# test_controller.net
KiCad netlist of a schematic drawn in EAGLE
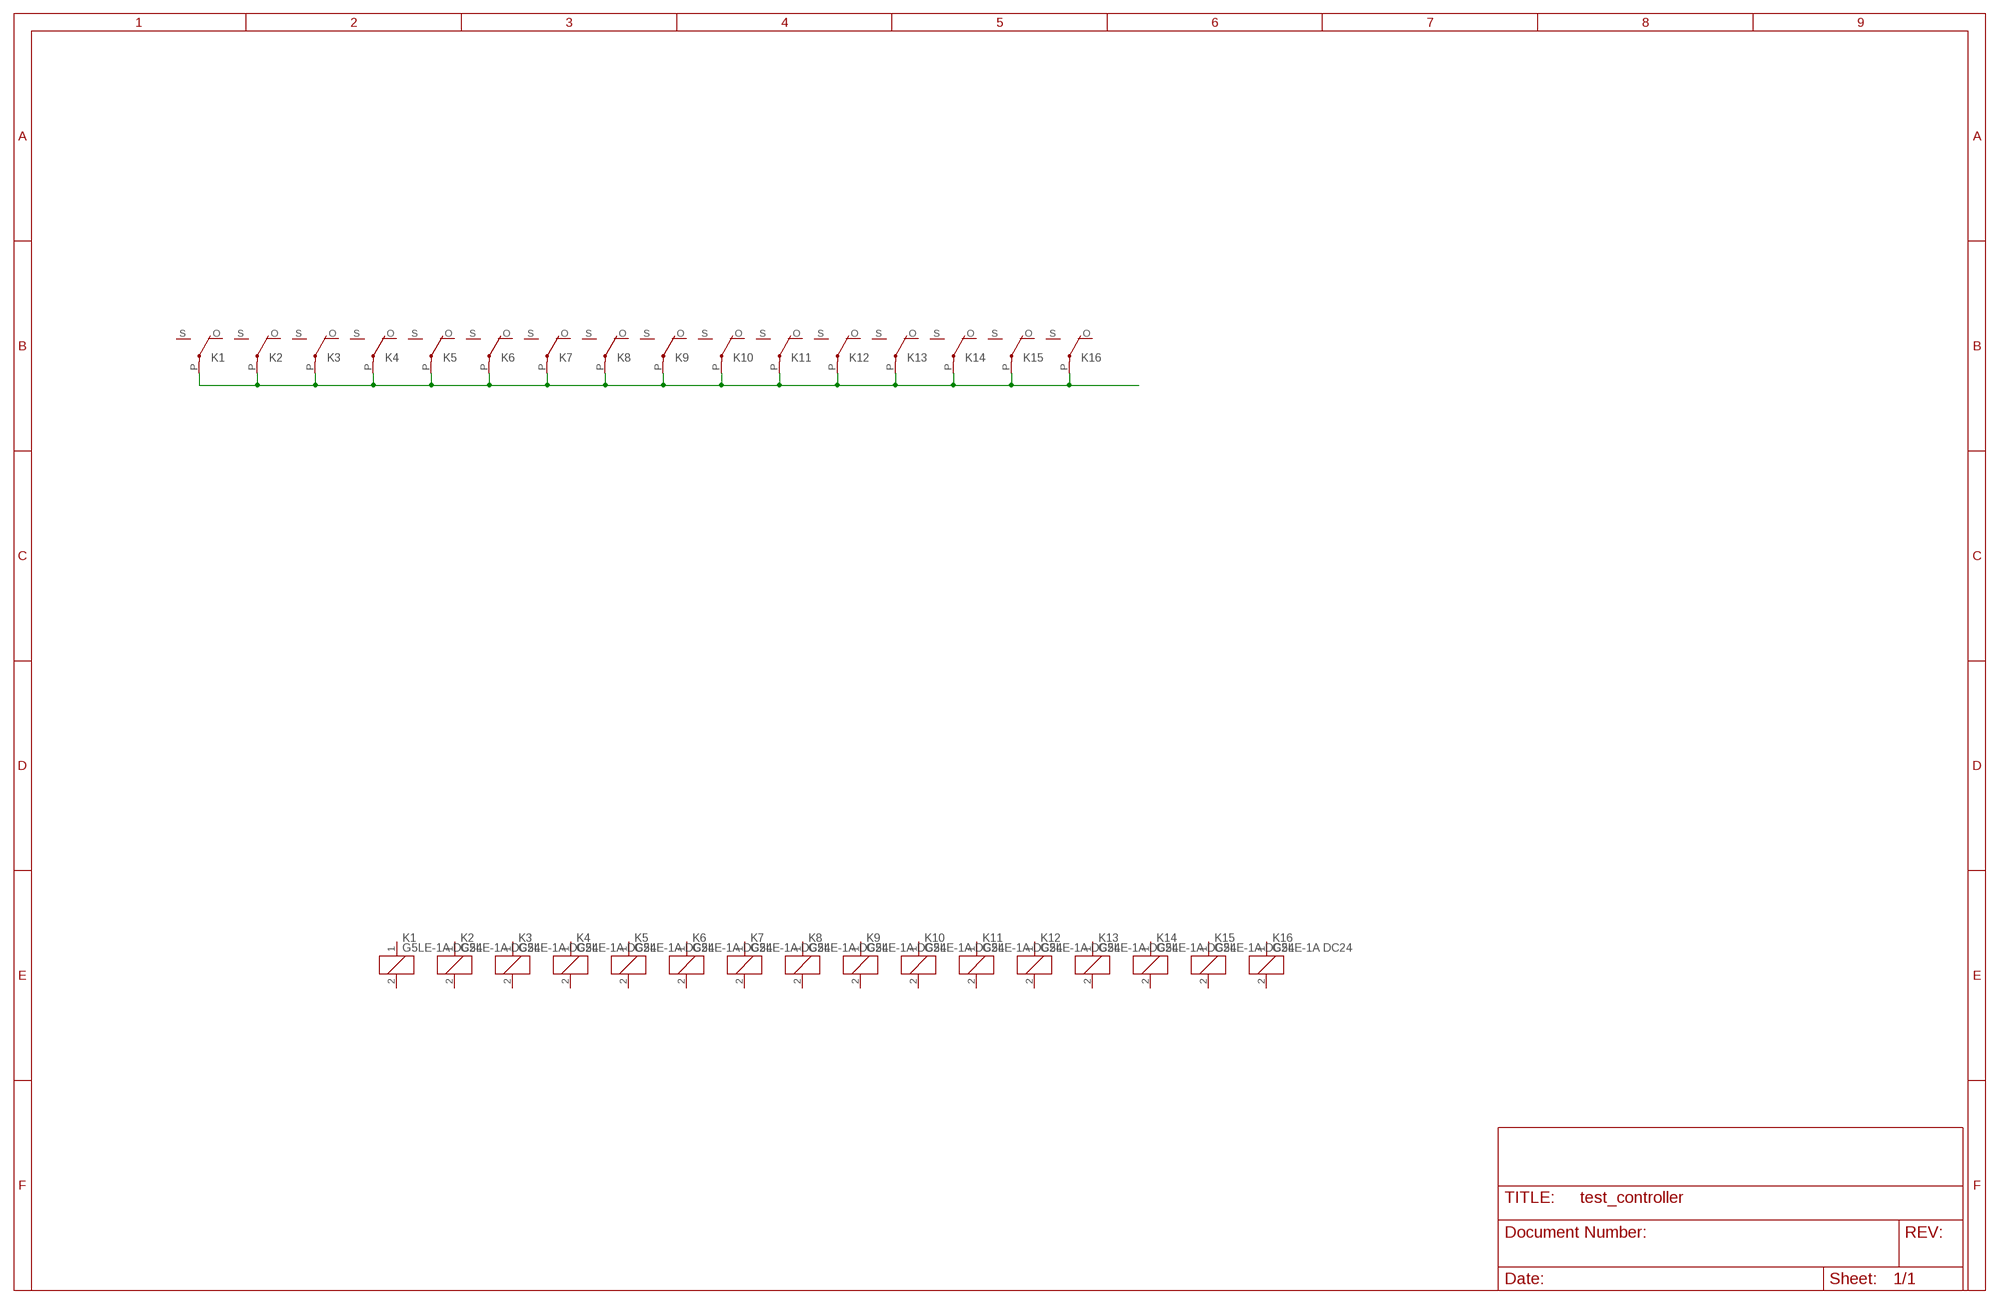
[diagram p0: schematic, sheet 1]

(export (version "E")
  (design (tool "Eeschema 10.0.6"))
  (components
    (comp (ref "K1")
      (value "G5LE-1A DC24")
      (footprint "eagle-import:G5LE")
      (libsource (lib "eagle-import") (part "G5LE"))
    )
    (comp (ref "K2")
      (value "G5LE-1A DC24")
      (footprint "eagle-import:G5LE")
      (libsource (lib "eagle-import") (part "G5LE"))
    )
    (comp (ref "K3")
      (value "G5LE-1A DC24")
      (footprint "eagle-import:G5LE")
      (libsource (lib "eagle-import") (part "G5LE"))
    )
    (comp (ref "K4")
      (value "G5LE-1A DC24")
      (footprint "eagle-import:G5LE")
      (libsource (lib "eagle-import") (part "G5LE"))
    )
    (comp (ref "K5")
      (value "G5LE-1A DC24")
      (footprint "eagle-import:G5LE")
      (libsource (lib "eagle-import") (part "G5LE"))
    )
    (comp (ref "K6")
      (value "G5LE-1A DC24")
      (footprint "eagle-import:G5LE")
      (libsource (lib "eagle-import") (part "G5LE"))
    )
    (comp (ref "K7")
      (value "G5LE-1A DC24")
      (footprint "eagle-import:G5LE")
      (libsource (lib "eagle-import") (part "G5LE"))
    )
    (comp (ref "K8")
      (value "G5LE-1A DC24")
      (footprint "eagle-import:G5LE")
      (libsource (lib "eagle-import") (part "G5LE"))
    )
    (comp (ref "K9")
      (value "G5LE-1A DC24")
      (footprint "eagle-import:G5LE")
      (libsource (lib "eagle-import") (part "G5LE"))
    )
    (comp (ref "K10")
      (value "G5LE-1A DC24")
      (footprint "eagle-import:G5LE")
      (libsource (lib "eagle-import") (part "G5LE"))
    )
    (comp (ref "K11")
      (value "G5LE-1A DC24")
      (footprint "eagle-import:G5LE")
      (libsource (lib "eagle-import") (part "G5LE"))
    )
    (comp (ref "K12")
      (value "G5LE-1A DC24")
      (footprint "eagle-import:G5LE")
      (libsource (lib "eagle-import") (part "G5LE"))
    )
    (comp (ref "K13")
      (value "G5LE-1A DC24")
      (footprint "eagle-import:G5LE")
      (libsource (lib "eagle-import") (part "G5LE"))
    )
    (comp (ref "K14")
      (value "G5LE-1A DC24")
      (footprint "eagle-import:G5LE")
      (libsource (lib "eagle-import") (part "G5LE"))
    )
    (comp (ref "K15")
      (value "G5LE-1A DC24")
      (footprint "eagle-import:G5LE")
      (libsource (lib "eagle-import") (part "G5LE"))
    )
    (comp (ref "K16")
      (value "G5LE-1A DC24")
      (footprint "eagle-import:G5LE")
      (libsource (lib "eagle-import") (part "G5LE"))
    )
  )
  (nets
    (net (code "1") (name "Net-(K1-PadP)") (class "Default")
      (node (ref "K1") (pin "P") (pinfunction "P_P") (pintype "passive"))
      (node (ref "K10") (pin "P") (pinfunction "P_P") (pintype "passive"))
      (node (ref "K11") (pin "P") (pinfunction "P_P") (pintype "passive"))
      (node (ref "K12") (pin "P") (pinfunction "P_P") (pintype "passive"))
      (node (ref "K13") (pin "P") (pinfunction "P_P") (pintype "passive"))
      (node (ref "K14") (pin "P") (pinfunction "P_P") (pintype "passive"))
      (node (ref "K15") (pin "P") (pinfunction "P_P") (pintype "passive"))
      (node (ref "K16") (pin "P") (pinfunction "P_P") (pintype "passive"))
      (node (ref "K2") (pin "P") (pinfunction "P_P") (pintype "passive"))
      (node (ref "K3") (pin "P") (pinfunction "P_P") (pintype "passive"))
      (node (ref "K4") (pin "P") (pinfunction "P_P") (pintype "passive"))
      (node (ref "K5") (pin "P") (pinfunction "P_P") (pintype "passive"))
      (node (ref "K6") (pin "P") (pinfunction "P_P") (pintype "passive"))
      (node (ref "K7") (pin "P") (pinfunction "P_P") (pintype "passive"))
      (node (ref "K8") (pin "P") (pinfunction "P_P") (pintype "passive"))
      (node (ref "K9") (pin "P") (pinfunction "P_P") (pintype "passive"))
    )
    (net (code "2") (name "unconnected-(K1-Pad1)") (class "Default")
      (node (ref "K1") (pin "1") (pinfunction "1_1") (pintype "passive"))
    )
    (net (code "3") (name "unconnected-(K1-Pad2)") (class "Default")
      (node (ref "K1") (pin "2") (pinfunction "2_2") (pintype "passive"))
    )
    (net (code "4") (name "unconnected-(K1-PadO)") (class "Default")
      (node (ref "K1") (pin "O") (pinfunction "O_O") (pintype "passive"))
    )
    (net (code "5") (name "unconnected-(K1-PadS)") (class "Default")
      (node (ref "K1") (pin "S") (pinfunction "S_S") (pintype "passive"))
    )
    (net (code "6") (name "unconnected-(K2-Pad1)") (class "Default")
      (node (ref "K2") (pin "1") (pinfunction "1_1") (pintype "passive"))
    )
    (net (code "7") (name "unconnected-(K2-Pad2)") (class "Default")
      (node (ref "K2") (pin "2") (pinfunction "2_2") (pintype "passive"))
    )
    (net (code "8") (name "unconnected-(K2-PadO)") (class "Default")
      (node (ref "K2") (pin "O") (pinfunction "O_O") (pintype "passive"))
    )
    (net (code "9") (name "unconnected-(K2-PadS)") (class "Default")
      (node (ref "K2") (pin "S") (pinfunction "S_S") (pintype "passive"))
    )
    (net (code "10") (name "unconnected-(K3-Pad1)") (class "Default")
      (node (ref "K3") (pin "1") (pinfunction "1_1") (pintype "passive"))
    )
    (net (code "11") (name "unconnected-(K3-Pad2)") (class "Default")
      (node (ref "K3") (pin "2") (pinfunction "2_2") (pintype "passive"))
    )
    (net (code "12") (name "unconnected-(K3-PadO)") (class "Default")
      (node (ref "K3") (pin "O") (pinfunction "O_O") (pintype "passive"))
    )
    (net (code "13") (name "unconnected-(K3-PadS)") (class "Default")
      (node (ref "K3") (pin "S") (pinfunction "S_S") (pintype "passive"))
    )
    (net (code "14") (name "unconnected-(K4-Pad1)") (class "Default")
      (node (ref "K4") (pin "1") (pinfunction "1_1") (pintype "passive"))
    )
    (net (code "15") (name "unconnected-(K4-Pad2)") (class "Default")
      (node (ref "K4") (pin "2") (pinfunction "2_2") (pintype "passive"))
    )
    (net (code "16") (name "unconnected-(K4-PadO)") (class "Default")
      (node (ref "K4") (pin "O") (pinfunction "O_O") (pintype "passive"))
    )
    (net (code "17") (name "unconnected-(K4-PadS)") (class "Default")
      (node (ref "K4") (pin "S") (pinfunction "S_S") (pintype "passive"))
    )
    (net (code "18") (name "unconnected-(K5-Pad1)") (class "Default")
      (node (ref "K5") (pin "1") (pinfunction "1_1") (pintype "passive"))
    )
    (net (code "19") (name "unconnected-(K5-Pad2)") (class "Default")
      (node (ref "K5") (pin "2") (pinfunction "2_2") (pintype "passive"))
    )
    (net (code "20") (name "unconnected-(K5-PadO)") (class "Default")
      (node (ref "K5") (pin "O") (pinfunction "O_O") (pintype "passive"))
    )
    (net (code "21") (name "unconnected-(K5-PadS)") (class "Default")
      (node (ref "K5") (pin "S") (pinfunction "S_S") (pintype "passive"))
    )
    (net (code "22") (name "unconnected-(K6-Pad1)") (class "Default")
      (node (ref "K6") (pin "1") (pinfunction "1_1") (pintype "passive"))
    )
    (net (code "23") (name "unconnected-(K6-Pad2)") (class "Default")
      (node (ref "K6") (pin "2") (pinfunction "2_2") (pintype "passive"))
    )
    (net (code "24") (name "unconnected-(K6-PadO)") (class "Default")
      (node (ref "K6") (pin "O") (pinfunction "O_O") (pintype "passive"))
    )
    (net (code "25") (name "unconnected-(K6-PadS)") (class "Default")
      (node (ref "K6") (pin "S") (pinfunction "S_S") (pintype "passive"))
    )
    (net (code "26") (name "unconnected-(K7-Pad1)") (class "Default")
      (node (ref "K7") (pin "1") (pinfunction "1_1") (pintype "passive"))
    )
    (net (code "27") (name "unconnected-(K7-Pad2)") (class "Default")
      (node (ref "K7") (pin "2") (pinfunction "2_2") (pintype "passive"))
    )
    (net (code "28") (name "unconnected-(K7-PadO)") (class "Default")
      (node (ref "K7") (pin "O") (pinfunction "O_O") (pintype "passive"))
    )
    (net (code "29") (name "unconnected-(K7-PadS)") (class "Default")
      (node (ref "K7") (pin "S") (pinfunction "S_S") (pintype "passive"))
    )
    (net (code "30") (name "unconnected-(K8-Pad1)") (class "Default")
      (node (ref "K8") (pin "1") (pinfunction "1_1") (pintype "passive"))
    )
    (net (code "31") (name "unconnected-(K8-Pad2)") (class "Default")
      (node (ref "K8") (pin "2") (pinfunction "2_2") (pintype "passive"))
    )
    (net (code "32") (name "unconnected-(K8-PadO)") (class "Default")
      (node (ref "K8") (pin "O") (pinfunction "O_O") (pintype "passive"))
    )
    (net (code "33") (name "unconnected-(K8-PadS)") (class "Default")
      (node (ref "K8") (pin "S") (pinfunction "S_S") (pintype "passive"))
    )
    (net (code "34") (name "unconnected-(K9-Pad1)") (class "Default")
      (node (ref "K9") (pin "1") (pinfunction "1_1") (pintype "passive"))
    )
    (net (code "35") (name "unconnected-(K9-Pad2)") (class "Default")
      (node (ref "K9") (pin "2") (pinfunction "2_2") (pintype "passive"))
    )
    (net (code "36") (name "unconnected-(K9-PadO)") (class "Default")
      (node (ref "K9") (pin "O") (pinfunction "O_O") (pintype "passive"))
    )
    (net (code "37") (name "unconnected-(K9-PadS)") (class "Default")
      (node (ref "K9") (pin "S") (pinfunction "S_S") (pintype "passive"))
    )
    (net (code "38") (name "unconnected-(K10-Pad1)") (class "Default")
      (node (ref "K10") (pin "1") (pinfunction "1_1") (pintype "passive"))
    )
    (net (code "39") (name "unconnected-(K10-Pad2)") (class "Default")
      (node (ref "K10") (pin "2") (pinfunction "2_2") (pintype "passive"))
    )
    (net (code "40") (name "unconnected-(K10-PadO)") (class "Default")
      (node (ref "K10") (pin "O") (pinfunction "O_O") (pintype "passive"))
    )
    (net (code "41") (name "unconnected-(K10-PadS)") (class "Default")
      (node (ref "K10") (pin "S") (pinfunction "S_S") (pintype "passive"))
    )
    (net (code "42") (name "unconnected-(K11-Pad1)") (class "Default")
      (node (ref "K11") (pin "1") (pinfunction "1_1") (pintype "passive"))
    )
    (net (code "43") (name "unconnected-(K11-Pad2)") (class "Default")
      (node (ref "K11") (pin "2") (pinfunction "2_2") (pintype "passive"))
    )
    (net (code "44") (name "unconnected-(K11-PadO)") (class "Default")
      (node (ref "K11") (pin "O") (pinfunction "O_O") (pintype "passive"))
    )
    (net (code "45") (name "unconnected-(K11-PadS)") (class "Default")
      (node (ref "K11") (pin "S") (pinfunction "S_S") (pintype "passive"))
    )
    (net (code "46") (name "unconnected-(K12-Pad1)") (class "Default")
      (node (ref "K12") (pin "1") (pinfunction "1_1") (pintype "passive"))
    )
    (net (code "47") (name "unconnected-(K12-Pad2)") (class "Default")
      (node (ref "K12") (pin "2") (pinfunction "2_2") (pintype "passive"))
    )
    (net (code "48") (name "unconnected-(K12-PadO)") (class "Default")
      (node (ref "K12") (pin "O") (pinfunction "O_O") (pintype "passive"))
    )
    (net (code "49") (name "unconnected-(K12-PadS)") (class "Default")
      (node (ref "K12") (pin "S") (pinfunction "S_S") (pintype "passive"))
    )
    (net (code "50") (name "unconnected-(K13-Pad1)") (class "Default")
      (node (ref "K13") (pin "1") (pinfunction "1_1") (pintype "passive"))
    )
    (net (code "51") (name "unconnected-(K13-Pad2)") (class "Default")
      (node (ref "K13") (pin "2") (pinfunction "2_2") (pintype "passive"))
    )
    (net (code "52") (name "unconnected-(K13-PadO)") (class "Default")
      (node (ref "K13") (pin "O") (pinfunction "O_O") (pintype "passive"))
    )
    (net (code "53") (name "unconnected-(K13-PadS)") (class "Default")
      (node (ref "K13") (pin "S") (pinfunction "S_S") (pintype "passive"))
    )
    (net (code "54") (name "unconnected-(K14-Pad1)") (class "Default")
      (node (ref "K14") (pin "1") (pinfunction "1_1") (pintype "passive"))
    )
    (net (code "55") (name "unconnected-(K14-Pad2)") (class "Default")
      (node (ref "K14") (pin "2") (pinfunction "2_2") (pintype "passive"))
    )
    (net (code "56") (name "unconnected-(K14-PadO)") (class "Default")
      (node (ref "K14") (pin "O") (pinfunction "O_O") (pintype "passive"))
    )
    (net (code "57") (name "unconnected-(K14-PadS)") (class "Default")
      (node (ref "K14") (pin "S") (pinfunction "S_S") (pintype "passive"))
    )
    (net (code "58") (name "unconnected-(K15-Pad1)") (class "Default")
      (node (ref "K15") (pin "1") (pinfunction "1_1") (pintype "passive"))
    )
    (net (code "59") (name "unconnected-(K15-Pad2)") (class "Default")
      (node (ref "K15") (pin "2") (pinfunction "2_2") (pintype "passive"))
    )
    (net (code "60") (name "unconnected-(K15-PadO)") (class "Default")
      (node (ref "K15") (pin "O") (pinfunction "O_O") (pintype "passive"))
    )
    (net (code "61") (name "unconnected-(K15-PadS)") (class "Default")
      (node (ref "K15") (pin "S") (pinfunction "S_S") (pintype "passive"))
    )
    (net (code "62") (name "unconnected-(K16-Pad1)") (class "Default")
      (node (ref "K16") (pin "1") (pinfunction "1_1") (pintype "passive"))
    )
    (net (code "63") (name "unconnected-(K16-Pad2)") (class "Default")
      (node (ref "K16") (pin "2") (pinfunction "2_2") (pintype "passive"))
    )
    (net (code "64") (name "unconnected-(K16-PadO)") (class "Default")
      (node (ref "K16") (pin "O") (pinfunction "O_O") (pintype "passive"))
    )
    (net (code "65") (name "unconnected-(K16-PadS)") (class "Default")
      (node (ref "K16") (pin "S") (pinfunction "S_S") (pintype "passive"))
    )
  )
)
